# spinduino-apa102.net
KiCad netlist of a schematic drawn in EAGLE
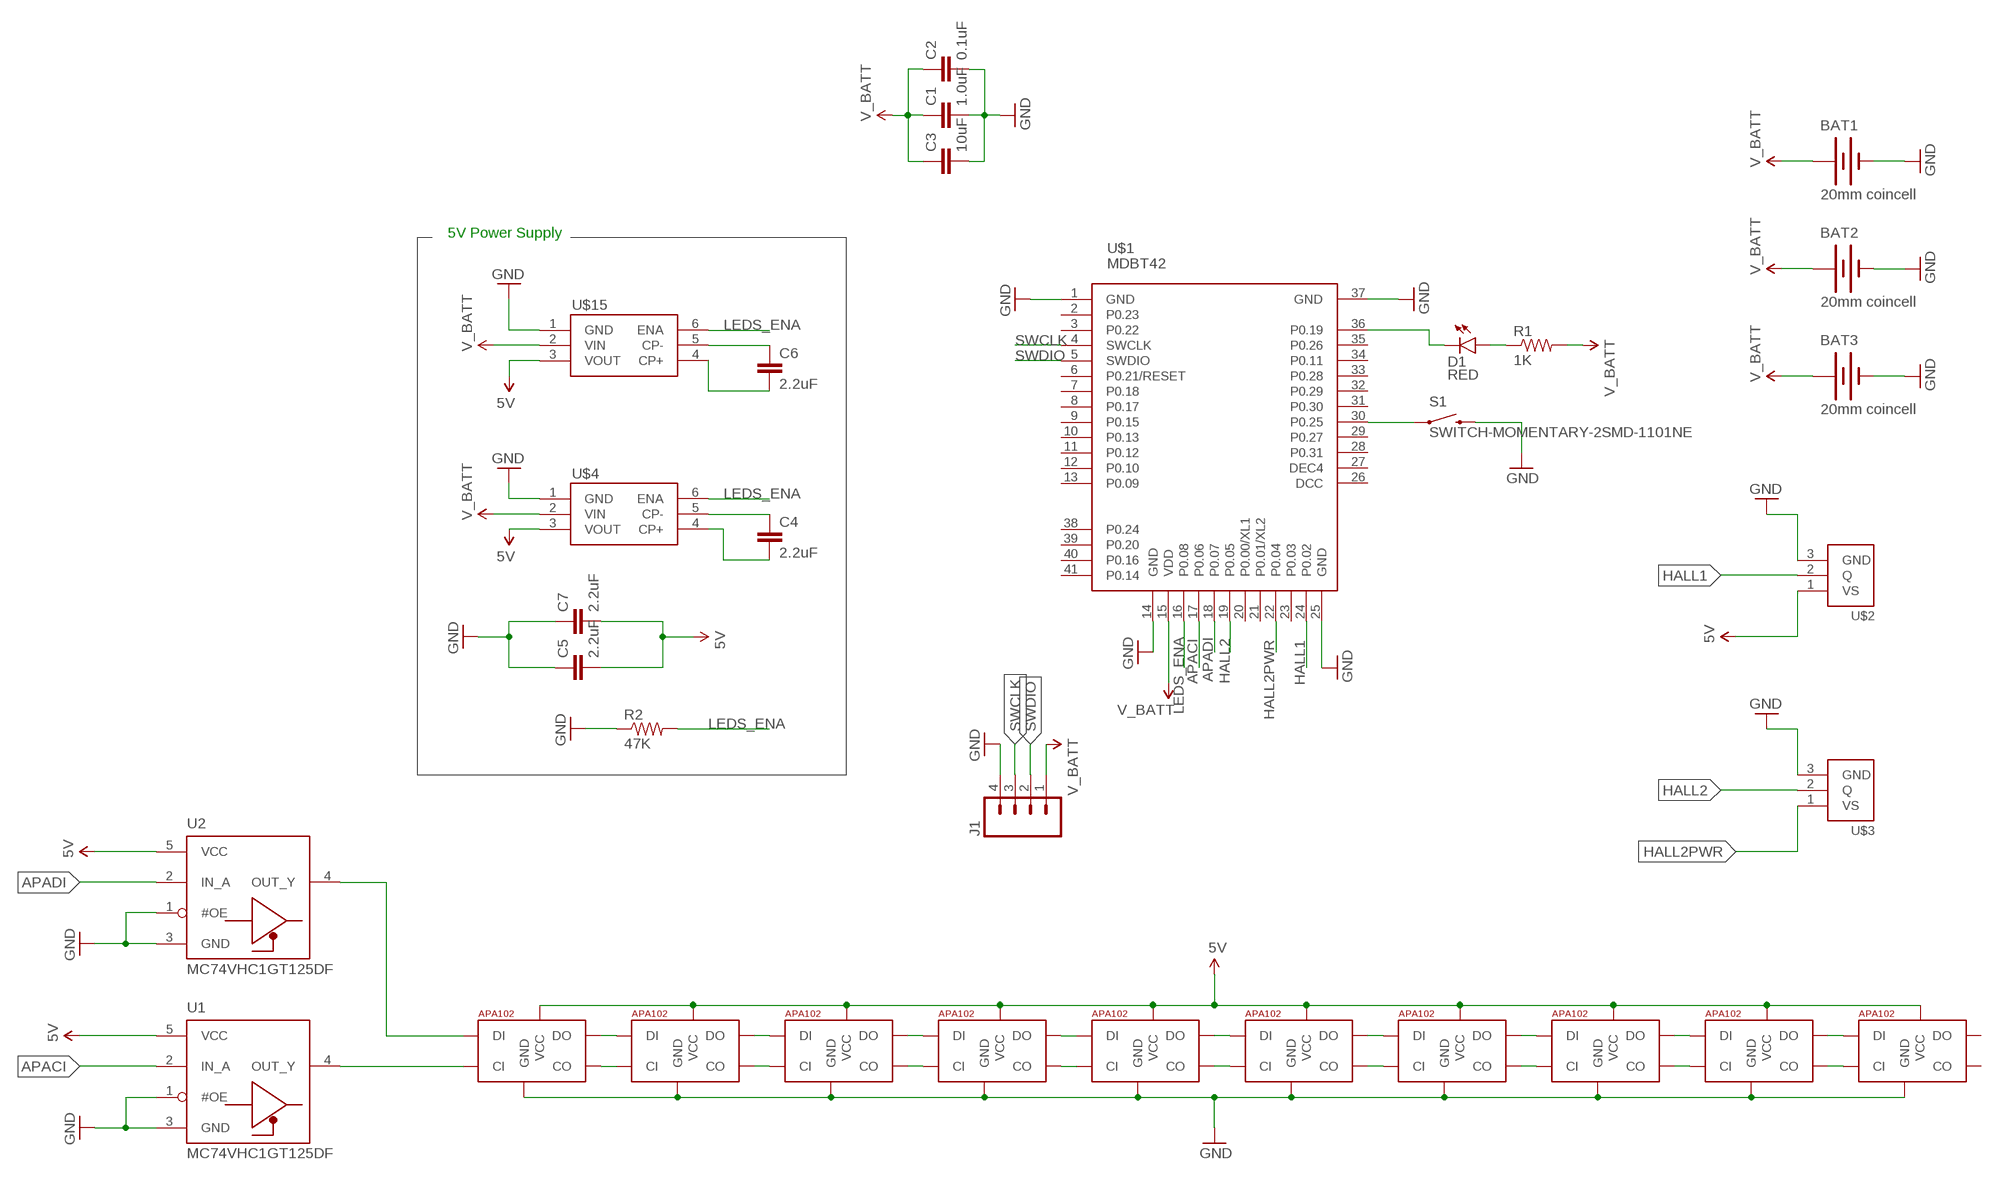
[diagram p0: schematic, sheet 1]

(export (version "E")
  (design (tool "Eeschema 10.0.6"))
  (components
    (comp (ref "BAT1")
      (value "20mm coincell")
      (footprint "eagle-import:BATTCON_20MM_4LEGS")
      (libsource (lib "eagle-import") (part "BATTERY20MM_4LEGS"))
    )
    (comp (ref "BAT2")
      (value "20mm coincell")
      (footprint "eagle-import:BATTCON_20MM_4LEGS")
      (libsource (lib "eagle-import") (part "BATTERY20MM_4LEGS"))
    )
    (comp (ref "BAT3")
      (value "20mm coincell")
      (footprint "eagle-import:BATTCON_20MM_4LEGS")
      (libsource (lib "eagle-import") (part "BATTERY20MM_4LEGS"))
    )
    (comp (ref "C1")
      (value "1.0uF")
      (footprint "eagle-import:0603-CAP")
      (libsource (lib "eagle-import") (part "1.0UF-16V-10%(0603)"))
    )
    (comp (ref "C2")
      (value "0.1uF")
      (footprint "eagle-import:0603-CAP")
      (libsource (lib "eagle-import") (part "0.1UF-25V-5%(0603)"))
    )
    (comp (ref "C3")
      (value "10uF")
      (footprint "eagle-import:0603-CAP")
      (libsource (lib "eagle-import") (part "10UF-6.3V-20%(0603)"))
    )
    (comp (ref "C4")
      (value "2.2uF")
      (footprint "eagle-import:0603-CAP")
      (libsource (lib "eagle-import") (part "2.2UF-10V-20%(0603)"))
    )
    (comp (ref "C5")
      (value "2.2uF")
      (footprint "eagle-import:0603-CAP")
      (libsource (lib "eagle-import") (part "10UF-6.3V-20%(0603)"))
    )
    (comp (ref "C6")
      (value "2.2uF")
      (footprint "eagle-import:0603-CAP")
      (libsource (lib "eagle-import") (part "2.2UF-10V-20%(0603)"))
    )
    (comp (ref "C7")
      (value "2.2uF")
      (footprint "eagle-import:0603-CAP")
      (libsource (lib "eagle-import") (part "10UF-6.3V-20%(0603)"))
    )
    (comp (ref "D1")
      (value "RED")
      (footprint "eagle-import:LED-0603")
      (libsource (lib "eagle-import") (part "LED-RED0603"))
    )
    (comp (ref "J1")
      (value "M04LOCK")
      (footprint "eagle-import:1X04_LOCK")
      (libsource (lib "eagle-import") (part "M04LOCK"))
    )
    (comp (ref "R1")
      (value "1K")
      (footprint "eagle-import:0603-RES")
      (libsource (lib "eagle-import") (part "1KOHM-1/10W-1%(0603)"))
    )
    (comp (ref "R2")
      (value "47K")
      (footprint "eagle-import:0603-RES")
      (libsource (lib "eagle-import") (part "1KOHM-1/10W-1%(0603)"))
    )
    (comp (ref "S1")
      (value "SWITCH-MOMENTARY-2SMD-1101NE")
      (footprint "eagle-import:TACTILE-SWITCH-1101NE")
      (libsource (lib "eagle-import") (part "SWITCH-MOMENTARY-2SMD-1101NE"))
    )
    (comp (ref "U$1")
      (value "MDBT42")
      (footprint "eagle-import:MDBT42")
      (libsource (lib "eagle-import") (part "MDBT42"))
    )
    (comp (ref "U$2")
      (value "TLE4946-2KSMD")
      (footprint "eagle-import:SC-59")
      (libsource (lib "eagle-import") (part "TLE4946-2KSMD"))
    )
    (comp (ref "U$3")
      (value "TLE4946-2KSMD")
      (footprint "eagle-import:SC-59")
      (libsource (lib "eagle-import") (part "TLE4946-2KSMD"))
    )
    (comp (ref "U$4")
      (value "TPS60150")
      (footprint "eagle-import:WSON6")
      (libsource (lib "eagle-import") (part "TPS60150"))
    )
    (comp (ref "U$5")
      (value "APA1022020")
      (footprint "eagle-import:APA102_2020")
      (libsource (lib "eagle-import") (part "APA1022020"))
    )
    (comp (ref "U$6")
      (value "APA1022020")
      (footprint "eagle-import:APA102_2020")
      (libsource (lib "eagle-import") (part "APA1022020"))
    )
    (comp (ref "U$7")
      (value "APA1022020")
      (footprint "eagle-import:APA102_2020")
      (libsource (lib "eagle-import") (part "APA1022020"))
    )
    (comp (ref "U$8")
      (value "APA1022020")
      (footprint "eagle-import:APA102_2020")
      (libsource (lib "eagle-import") (part "APA1022020"))
    )
    (comp (ref "U$9")
      (value "APA1022020")
      (footprint "eagle-import:APA102_2020")
      (libsource (lib "eagle-import") (part "APA1022020"))
    )
    (comp (ref "U$10")
      (value "APA1022020")
      (footprint "eagle-import:APA102_2020")
      (libsource (lib "eagle-import") (part "APA1022020"))
    )
    (comp (ref "U$11")
      (value "APA1022020")
      (footprint "eagle-import:APA102_2020")
      (libsource (lib "eagle-import") (part "APA1022020"))
    )
    (comp (ref "U$12")
      (value "APA1022020")
      (footprint "eagle-import:APA102_2020")
      (libsource (lib "eagle-import") (part "APA1022020"))
    )
    (comp (ref "U$13")
      (value "APA1022020")
      (footprint "eagle-import:APA102_2020")
      (libsource (lib "eagle-import") (part "APA1022020"))
    )
    (comp (ref "U$14")
      (value "APA1022020")
      (footprint "eagle-import:APA102_2020")
      (libsource (lib "eagle-import") (part "APA1022020"))
    )
    (comp (ref "U$15")
      (value "TPS60150")
      (footprint "eagle-import:WSON6")
      (libsource (lib "eagle-import") (part "TPS60150"))
    )
    (comp (ref "U1")
      (value "MC74VHC1GT125DF")
      (footprint "eagle-import:SOT353")
      (libsource (lib "eagle-import") (part "MC74VHC1GT125DF"))
    )
    (comp (ref "U2")
      (value "MC74VHC1GT125DF")
      (footprint "eagle-import:SOT353")
      (libsource (lib "eagle-import") (part "MC74VHC1GT125DF"))
    )
  )
  (nets
    (net (code "1") (name "/LEDS_ENA") (class "Default")
      (node (ref "R2") (pin "2") (pinfunction "2_2") (pintype "passive"))
      (node (ref "U$1") (pin "16") (pinfunction "P0.08_16") (pintype "bidirectional"))
      (node (ref "U$15") (pin "6") (pinfunction "ENA_6") (pintype "input"))
      (node (ref "U$4") (pin "6") (pinfunction "ENA_6") (pintype "input"))
    )
    (net (code "2") (name "5V") (class "Default")
      (node (ref "C5") (pin "2") (pinfunction "2_2") (pintype "passive"))
      (node (ref "C7") (pin "2") (pinfunction "2_2") (pintype "passive"))
      (node (ref "U$10") (pin "V_CC") (pinfunction "VCC_V_CC") (pintype "bidirectional"))
      (node (ref "U$11") (pin "V_CC") (pinfunction "VCC_V_CC") (pintype "bidirectional"))
      (node (ref "U$12") (pin "V_CC") (pinfunction "VCC_V_CC") (pintype "bidirectional"))
      (node (ref "U$13") (pin "V_CC") (pinfunction "VCC_V_CC") (pintype "bidirectional"))
      (node (ref "U$14") (pin "V_CC") (pinfunction "VCC_V_CC") (pintype "bidirectional"))
      (node (ref "U$15") (pin "3") (pinfunction "VOUT_3") (pintype "power_in"))
      (node (ref "U$2") (pin "1") (pinfunction "VS_1") (pintype "bidirectional"))
      (node (ref "U$4") (pin "3") (pinfunction "VOUT_3") (pintype "power_in"))
      (node (ref "U$5") (pin "V_CC") (pinfunction "VCC_V_CC") (pintype "bidirectional"))
      (node (ref "U$6") (pin "V_CC") (pinfunction "VCC_V_CC") (pintype "bidirectional"))
      (node (ref "U$7") (pin "V_CC") (pinfunction "VCC_V_CC") (pintype "bidirectional"))
      (node (ref "U$8") (pin "V_CC") (pinfunction "VCC_V_CC") (pintype "bidirectional"))
      (node (ref "U$9") (pin "V_CC") (pinfunction "VCC_V_CC") (pintype "bidirectional"))
      (node (ref "U1") (pin "5") (pinfunction "VCC_5") (pintype "power_in"))
      (node (ref "U2") (pin "5") (pinfunction "VCC_5") (pintype "power_in"))
    )
    (net (code "3") (name "APACI") (class "Default")
      (node (ref "U$1") (pin "17") (pinfunction "P0.06_17") (pintype "bidirectional"))
      (node (ref "U1") (pin "2") (pinfunction "IN_A_2") (pintype "bidirectional"))
    )
    (net (code "4") (name "APADI") (class "Default")
      (node (ref "U$1") (pin "18") (pinfunction "P0.07_18") (pintype "bidirectional"))
      (node (ref "U2") (pin "2") (pinfunction "IN_A_2") (pintype "bidirectional"))
    )
    (net (code "5") (name "GND") (class "Default")
      (node (ref "BAT1") (pin "NEGATIVE") (pinfunction "-_NEGATIVE") (pintype "power_in"))
      (node (ref "BAT2") (pin "NEGATIVE") (pinfunction "-_NEGATIVE") (pintype "power_in"))
      (node (ref "BAT3") (pin "NEGATIVE") (pinfunction "-_NEGATIVE") (pintype "power_in"))
      (node (ref "C1") (pin "2") (pinfunction "2_2") (pintype "passive"))
      (node (ref "C2") (pin "2") (pinfunction "2_2") (pintype "passive"))
      (node (ref "C3") (pin "2") (pinfunction "2_2") (pintype "passive"))
      (node (ref "C5") (pin "1") (pinfunction "1_1") (pintype "passive"))
      (node (ref "C7") (pin "1") (pinfunction "1_1") (pintype "passive"))
      (node (ref "J1") (pin "4") (pinfunction "4_4") (pintype "passive"))
      (node (ref "R2") (pin "1") (pinfunction "1_1") (pintype "passive"))
      (node (ref "S1") (pin "2") (pinfunction "2_2") (pintype "passive"))
      (node (ref "U$1") (pin "1") (pinfunction "GND_1") (pintype "bidirectional"))
      (node (ref "U$1") (pin "14") (pinfunction "GND_14") (pintype "bidirectional"))
      (node (ref "U$1") (pin "25") (pinfunction "GND_25") (pintype "bidirectional"))
      (node (ref "U$1") (pin "37") (pinfunction "GND_37") (pintype "bidirectional"))
      (node (ref "U$10") (pin "GND") (pinfunction "GND_GND") (pintype "bidirectional"))
      (node (ref "U$11") (pin "GND") (pinfunction "GND_GND") (pintype "bidirectional"))
      (node (ref "U$12") (pin "GND") (pinfunction "GND_GND") (pintype "bidirectional"))
      (node (ref "U$13") (pin "GND") (pinfunction "GND_GND") (pintype "bidirectional"))
      (node (ref "U$14") (pin "GND") (pinfunction "GND_GND") (pintype "bidirectional"))
      (node (ref "U$15") (pin "1") (pinfunction "GND_1") (pintype "power_in"))
      (node (ref "U$2") (pin "3") (pinfunction "GND_3") (pintype "bidirectional"))
      (node (ref "U$3") (pin "3") (pinfunction "GND_3") (pintype "bidirectional"))
      (node (ref "U$4") (pin "1") (pinfunction "GND_1") (pintype "power_in"))
      (node (ref "U$5") (pin "GND") (pinfunction "GND_GND") (pintype "bidirectional"))
      (node (ref "U$6") (pin "GND") (pinfunction "GND_GND") (pintype "bidirectional"))
      (node (ref "U$7") (pin "GND") (pinfunction "GND_GND") (pintype "bidirectional"))
      (node (ref "U$8") (pin "GND") (pinfunction "GND_GND") (pintype "bidirectional"))
      (node (ref "U$9") (pin "GND") (pinfunction "GND_GND") (pintype "bidirectional"))
      (node (ref "U1") (pin "1") (pinfunction "#OE_1") (pintype "input"))
      (node (ref "U1") (pin "3") (pinfunction "GND_3") (pintype "power_in"))
      (node (ref "U2") (pin "1") (pinfunction "#OE_1") (pintype "input"))
      (node (ref "U2") (pin "3") (pinfunction "GND_3") (pintype "power_in"))
    )
    (net (code "6") (name "HALL1") (class "Default")
      (node (ref "U$1") (pin "24") (pinfunction "P0.02_24") (pintype "bidirectional"))
      (node (ref "U$2") (pin "2") (pinfunction "Q_2") (pintype "bidirectional"))
    )
    (net (code "7") (name "HALL2") (class "Default")
      (node (ref "U$1") (pin "19") (pinfunction "P0.05_19") (pintype "bidirectional"))
      (node (ref "U$3") (pin "2") (pinfunction "Q_2") (pintype "bidirectional"))
    )
    (net (code "8") (name "HALL2PWR") (class "Default")
      (node (ref "U$1") (pin "22") (pinfunction "P0.04_22") (pintype "bidirectional"))
      (node (ref "U$3") (pin "1") (pinfunction "VS_1") (pintype "bidirectional"))
    )
    (net (code "9") (name "Net-(D1-PadA)") (class "Default")
      (node (ref "D1") (pin "A") (pinfunction "A_A") (pintype "passive"))
      (node (ref "R1") (pin "1") (pinfunction "1_1") (pintype "passive"))
    )
    (net (code "10") (name "Net-(U$1-P0.19)") (class "Default")
      (node (ref "D1") (pin "C") (pinfunction "C_C") (pintype "passive"))
      (node (ref "U$1") (pin "36") (pinfunction "P0.19_36") (pintype "bidirectional"))
    )
    (net (code "11") (name "Net-(U$1-P0.25)") (class "Default")
      (node (ref "S1") (pin "1") (pinfunction "1_1") (pintype "passive"))
      (node (ref "U$1") (pin "30") (pinfunction "P0.25_30") (pintype "bidirectional"))
    )
    (net (code "12") (name "Net-(U$4-CP+)") (class "Default")
      (node (ref "C4") (pin "2") (pinfunction "2_2") (pintype "passive"))
      (node (ref "U$4") (pin "4") (pinfunction "CP+_4") (pintype "bidirectional"))
    )
    (net (code "13") (name "Net-(U$4-CP-)") (class "Default")
      (node (ref "C4") (pin "1") (pinfunction "1_1") (pintype "passive"))
      (node (ref "U$4") (pin "5") (pinfunction "CP-_5") (pintype "bidirectional"))
    )
    (net (code "14") (name "Net-(U$5-CI)") (class "Default")
      (node (ref "U$5") (pin "C_IN") (pinfunction "CI_C_IN") (pintype "bidirectional"))
      (node (ref "U$6") (pin "CL_OUT") (pinfunction "CO_CL_OUT") (pintype "bidirectional"))
    )
    (net (code "15") (name "Net-(U$5-DI)") (class "Default")
      (node (ref "U$5") (pin "D_IN") (pinfunction "DI_D_IN") (pintype "bidirectional"))
      (node (ref "U$6") (pin "D_OUT") (pinfunction "DO_D_OUT") (pintype "bidirectional"))
    )
    (net (code "16") (name "Net-(U$6-CI)") (class "Default")
      (node (ref "U$6") (pin "C_IN") (pinfunction "CI_C_IN") (pintype "bidirectional"))
      (node (ref "U$7") (pin "CL_OUT") (pinfunction "CO_CL_OUT") (pintype "bidirectional"))
    )
    (net (code "17") (name "Net-(U$6-DI)") (class "Default")
      (node (ref "U$6") (pin "D_IN") (pinfunction "DI_D_IN") (pintype "bidirectional"))
      (node (ref "U$7") (pin "D_OUT") (pinfunction "DO_D_OUT") (pintype "bidirectional"))
    )
    (net (code "18") (name "Net-(U$7-CI)") (class "Default")
      (node (ref "U$7") (pin "C_IN") (pinfunction "CI_C_IN") (pintype "bidirectional"))
      (node (ref "U$8") (pin "CL_OUT") (pinfunction "CO_CL_OUT") (pintype "bidirectional"))
    )
    (net (code "19") (name "Net-(U$7-DI)") (class "Default")
      (node (ref "U$7") (pin "D_IN") (pinfunction "DI_D_IN") (pintype "bidirectional"))
      (node (ref "U$8") (pin "D_OUT") (pinfunction "DO_D_OUT") (pintype "bidirectional"))
    )
    (net (code "20") (name "Net-(U$8-CI)") (class "Default")
      (node (ref "U$8") (pin "C_IN") (pinfunction "CI_C_IN") (pintype "bidirectional"))
      (node (ref "U$9") (pin "CL_OUT") (pinfunction "CO_CL_OUT") (pintype "bidirectional"))
    )
    (net (code "21") (name "Net-(U$8-DI)") (class "Default")
      (node (ref "U$8") (pin "D_IN") (pinfunction "DI_D_IN") (pintype "bidirectional"))
      (node (ref "U$9") (pin "D_OUT") (pinfunction "DO_D_OUT") (pintype "bidirectional"))
    )
    (net (code "22") (name "Net-(U$10-CI)") (class "Default")
      (node (ref "U$10") (pin "C_IN") (pinfunction "CI_C_IN") (pintype "bidirectional"))
      (node (ref "U$11") (pin "CL_OUT") (pinfunction "CO_CL_OUT") (pintype "bidirectional"))
    )
    (net (code "23") (name "Net-(U$10-CO)") (class "Default")
      (node (ref "U$10") (pin "CL_OUT") (pinfunction "CO_CL_OUT") (pintype "bidirectional"))
      (node (ref "U$9") (pin "C_IN") (pinfunction "CI_C_IN") (pintype "bidirectional"))
    )
    (net (code "24") (name "Net-(U$10-DI)") (class "Default")
      (node (ref "U$10") (pin "D_IN") (pinfunction "DI_D_IN") (pintype "bidirectional"))
      (node (ref "U$11") (pin "D_OUT") (pinfunction "DO_D_OUT") (pintype "bidirectional"))
    )
    (net (code "25") (name "Net-(U$10-DO)") (class "Default")
      (node (ref "U$10") (pin "D_OUT") (pinfunction "DO_D_OUT") (pintype "bidirectional"))
      (node (ref "U$9") (pin "D_IN") (pinfunction "DI_D_IN") (pintype "bidirectional"))
    )
    (net (code "26") (name "Net-(U$11-CI)") (class "Default")
      (node (ref "U$11") (pin "C_IN") (pinfunction "CI_C_IN") (pintype "bidirectional"))
      (node (ref "U$12") (pin "CL_OUT") (pinfunction "CO_CL_OUT") (pintype "bidirectional"))
    )
    (net (code "27") (name "Net-(U$11-DI)") (class "Default")
      (node (ref "U$11") (pin "D_IN") (pinfunction "DI_D_IN") (pintype "bidirectional"))
      (node (ref "U$12") (pin "D_OUT") (pinfunction "DO_D_OUT") (pintype "bidirectional"))
    )
    (net (code "28") (name "Net-(U$12-CI)") (class "Default")
      (node (ref "U$12") (pin "C_IN") (pinfunction "CI_C_IN") (pintype "bidirectional"))
      (node (ref "U$13") (pin "CL_OUT") (pinfunction "CO_CL_OUT") (pintype "bidirectional"))
    )
    (net (code "29") (name "Net-(U$12-DI)") (class "Default")
      (node (ref "U$12") (pin "D_IN") (pinfunction "DI_D_IN") (pintype "bidirectional"))
      (node (ref "U$13") (pin "D_OUT") (pinfunction "DO_D_OUT") (pintype "bidirectional"))
    )
    (net (code "30") (name "Net-(U$13-CI)") (class "Default")
      (node (ref "U$13") (pin "C_IN") (pinfunction "CI_C_IN") (pintype "bidirectional"))
      (node (ref "U$14") (pin "CL_OUT") (pinfunction "CO_CL_OUT") (pintype "bidirectional"))
    )
    (net (code "31") (name "Net-(U$13-DI)") (class "Default")
      (node (ref "U$13") (pin "D_IN") (pinfunction "DI_D_IN") (pintype "bidirectional"))
      (node (ref "U$14") (pin "D_OUT") (pinfunction "DO_D_OUT") (pintype "bidirectional"))
    )
    (net (code "32") (name "Net-(U$14-CI)") (class "Default")
      (node (ref "U$14") (pin "C_IN") (pinfunction "CI_C_IN") (pintype "bidirectional"))
      (node (ref "U1") (pin "4") (pinfunction "OUT_Y_4") (pintype "bidirectional"))
    )
    (net (code "33") (name "Net-(U$14-DI)") (class "Default")
      (node (ref "U$14") (pin "D_IN") (pinfunction "DI_D_IN") (pintype "bidirectional"))
      (node (ref "U2") (pin "4") (pinfunction "OUT_Y_4") (pintype "bidirectional"))
    )
    (net (code "34") (name "Net-(U$15-CP+)") (class "Default")
      (node (ref "C6") (pin "2") (pinfunction "2_2") (pintype "passive"))
      (node (ref "U$15") (pin "4") (pinfunction "CP+_4") (pintype "bidirectional"))
    )
    (net (code "35") (name "Net-(U$15-CP-)") (class "Default")
      (node (ref "C6") (pin "1") (pinfunction "1_1") (pintype "passive"))
      (node (ref "U$15") (pin "5") (pinfunction "CP-_5") (pintype "bidirectional"))
    )
    (net (code "36") (name "SWCLK") (class "Default")
      (node (ref "J1") (pin "3") (pinfunction "3_3") (pintype "passive"))
      (node (ref "U$1") (pin "4") (pinfunction "SWCLK_4") (pintype "bidirectional"))
    )
    (net (code "37") (name "SWDIO") (class "Default")
      (node (ref "J1") (pin "2") (pinfunction "2_2") (pintype "passive"))
      (node (ref "U$1") (pin "5") (pinfunction "SWDIO_5") (pintype "bidirectional"))
    )
    (net (code "38") (name "V_BATT") (class "Default")
      (node (ref "BAT1") (pin "POSITIVE@1") (pinfunction "+_POSITIVE@1") (pintype "power_in"))
      (node (ref "BAT1") (pin "POSITIVE@2") (pinfunction "+_POSITIVE@2") (pintype "power_in"))
      (node (ref "BAT1") (pin "POSITIVE@3") (pinfunction "+_POSITIVE@3") (pintype "power_in"))
      (node (ref "BAT1") (pin "POSITIVE@4") (pinfunction "+_POSITIVE@4") (pintype "power_in"))
      (node (ref "BAT2") (pin "POSITIVE@1") (pinfunction "+_POSITIVE@1") (pintype "power_in"))
      (node (ref "BAT2") (pin "POSITIVE@2") (pinfunction "+_POSITIVE@2") (pintype "power_in"))
      (node (ref "BAT2") (pin "POSITIVE@3") (pinfunction "+_POSITIVE@3") (pintype "power_in"))
      (node (ref "BAT2") (pin "POSITIVE@4") (pinfunction "+_POSITIVE@4") (pintype "power_in"))
      (node (ref "BAT3") (pin "POSITIVE@1") (pinfunction "+_POSITIVE@1") (pintype "power_in"))
      (node (ref "BAT3") (pin "POSITIVE@2") (pinfunction "+_POSITIVE@2") (pintype "power_in"))
      (node (ref "BAT3") (pin "POSITIVE@3") (pinfunction "+_POSITIVE@3") (pintype "power_in"))
      (node (ref "BAT3") (pin "POSITIVE@4") (pinfunction "+_POSITIVE@4") (pintype "power_in"))
      (node (ref "C1") (pin "1") (pinfunction "1_1") (pintype "passive"))
      (node (ref "C2") (pin "1") (pinfunction "1_1") (pintype "passive"))
      (node (ref "C3") (pin "1") (pinfunction "1_1") (pintype "passive"))
      (node (ref "J1") (pin "1") (pinfunction "1_1") (pintype "passive"))
      (node (ref "R1") (pin "2") (pinfunction "2_2") (pintype "passive"))
      (node (ref "U$1") (pin "15") (pinfunction "VDD_15") (pintype "bidirectional"))
      (node (ref "U$15") (pin "2") (pinfunction "VIN_2") (pintype "power_in"))
      (node (ref "U$4") (pin "2") (pinfunction "VIN_2") (pintype "power_in"))
    )
    (net (code "39") (name "unconnected-(U$1-DCC-Pad26)") (class "Default")
      (node (ref "U$1") (pin "26") (pinfunction "DCC_26") (pintype "bidirectional"))
    )
    (net (code "40") (name "unconnected-(U$1-DEC4-Pad27)") (class "Default")
      (node (ref "U$1") (pin "27") (pinfunction "DEC4_27") (pintype "bidirectional"))
    )
    (net (code "41") (name "unconnected-(U$1-P0.00{slash}XL1-Pad20)") (class "Default")
      (node (ref "U$1") (pin "20") (pinfunction "P0.00/XL1_20") (pintype "bidirectional"))
    )
    (net (code "42") (name "unconnected-(U$1-P0.01{slash}XL2-Pad21)") (class "Default")
      (node (ref "U$1") (pin "21") (pinfunction "P0.01/XL2_21") (pintype "bidirectional"))
    )
    (net (code "43") (name "unconnected-(U$1-P0.03-Pad23)") (class "Default")
      (node (ref "U$1") (pin "23") (pinfunction "P0.03_23") (pintype "bidirectional"))
    )
    (net (code "44") (name "unconnected-(U$1-P0.09-Pad13)") (class "Default")
      (node (ref "U$1") (pin "13") (pinfunction "P0.09_13") (pintype "bidirectional"))
    )
    (net (code "45") (name "unconnected-(U$1-P0.10-Pad12)") (class "Default")
      (node (ref "U$1") (pin "12") (pinfunction "P0.10_12") (pintype "bidirectional"))
    )
    (net (code "46") (name "unconnected-(U$1-P0.11-Pad34)") (class "Default")
      (node (ref "U$1") (pin "34") (pinfunction "P0.11_34") (pintype "bidirectional"))
    )
    (net (code "47") (name "unconnected-(U$1-P0.12-Pad11)") (class "Default")
      (node (ref "U$1") (pin "11") (pinfunction "P0.12_11") (pintype "bidirectional"))
    )
    (net (code "48") (name "unconnected-(U$1-P0.13-Pad10)") (class "Default")
      (node (ref "U$1") (pin "10") (pinfunction "P0.13_10") (pintype "bidirectional"))
    )
    (net (code "49") (name "unconnected-(U$1-P0.14-Pad41)") (class "Default")
      (node (ref "U$1") (pin "41") (pinfunction "P0.14_41") (pintype "bidirectional"))
    )
    (net (code "50") (name "unconnected-(U$1-P0.15-Pad9)") (class "Default")
      (node (ref "U$1") (pin "9") (pinfunction "P0.15_9") (pintype "bidirectional"))
    )
    (net (code "51") (name "unconnected-(U$1-P0.16-Pad40)") (class "Default")
      (node (ref "U$1") (pin "40") (pinfunction "P0.16_40") (pintype "bidirectional"))
    )
    (net (code "52") (name "unconnected-(U$1-P0.17-Pad8)") (class "Default")
      (node (ref "U$1") (pin "8") (pinfunction "P0.17_8") (pintype "bidirectional"))
    )
    (net (code "53") (name "unconnected-(U$1-P0.18-Pad7)") (class "Default")
      (node (ref "U$1") (pin "7") (pinfunction "P0.18_7") (pintype "bidirectional"))
    )
    (net (code "54") (name "unconnected-(U$1-P0.20-Pad39)") (class "Default")
      (node (ref "U$1") (pin "39") (pinfunction "P0.20_39") (pintype "bidirectional"))
    )
    (net (code "55") (name "unconnected-(U$1-P0.21{slash}RESET-Pad6)") (class "Default")
      (node (ref "U$1") (pin "6") (pinfunction "P0.21/RESET_6") (pintype "bidirectional"))
    )
    (net (code "56") (name "unconnected-(U$1-P0.22-Pad3)") (class "Default")
      (node (ref "U$1") (pin "3") (pinfunction "P0.22_3") (pintype "bidirectional"))
    )
    (net (code "57") (name "unconnected-(U$1-P0.23-Pad2)") (class "Default")
      (node (ref "U$1") (pin "2") (pinfunction "P0.23_2") (pintype "bidirectional"))
    )
    (net (code "58") (name "unconnected-(U$1-P0.24-Pad38)") (class "Default")
      (node (ref "U$1") (pin "38") (pinfunction "P0.24_38") (pintype "bidirectional"))
    )
    (net (code "59") (name "unconnected-(U$1-P0.26-Pad35)") (class "Default")
      (node (ref "U$1") (pin "35") (pinfunction "P0.26_35") (pintype "bidirectional"))
    )
    (net (code "60") (name "unconnected-(U$1-P0.27-Pad29)") (class "Default")
      (node (ref "U$1") (pin "29") (pinfunction "P0.27_29") (pintype "bidirectional"))
    )
    (net (code "61") (name "unconnected-(U$1-P0.28-Pad33)") (class "Default")
      (node (ref "U$1") (pin "33") (pinfunction "P0.28_33") (pintype "bidirectional"))
    )
    (net (code "62") (name "unconnected-(U$1-P0.29-Pad32)") (class "Default")
      (node (ref "U$1") (pin "32") (pinfunction "P0.29_32") (pintype "bidirectional"))
    )
    (net (code "63") (name "unconnected-(U$1-P0.30-Pad31)") (class "Default")
      (node (ref "U$1") (pin "31") (pinfunction "P0.30_31") (pintype "bidirectional"))
    )
    (net (code "64") (name "unconnected-(U$1-P0.31-Pad28)") (class "Default")
      (node (ref "U$1") (pin "28") (pinfunction "P0.31_28") (pintype "bidirectional"))
    )
    (net (code "65") (name "unconnected-(U$5-CO-PadCL_OUT)") (class "Default")
      (node (ref "U$5") (pin "CL_OUT") (pinfunction "CO_CL_OUT") (pintype "bidirectional"))
    )
    (net (code "66") (name "unconnected-(U$5-DO-PadD_OUT)") (class "Default")
      (node (ref "U$5") (pin "D_OUT") (pinfunction "DO_D_OUT") (pintype "bidirectional"))
    )
  )
)
